# HV_PWR_STAGE.net
KiCad netlist of a schematic drawn in Altium Designer
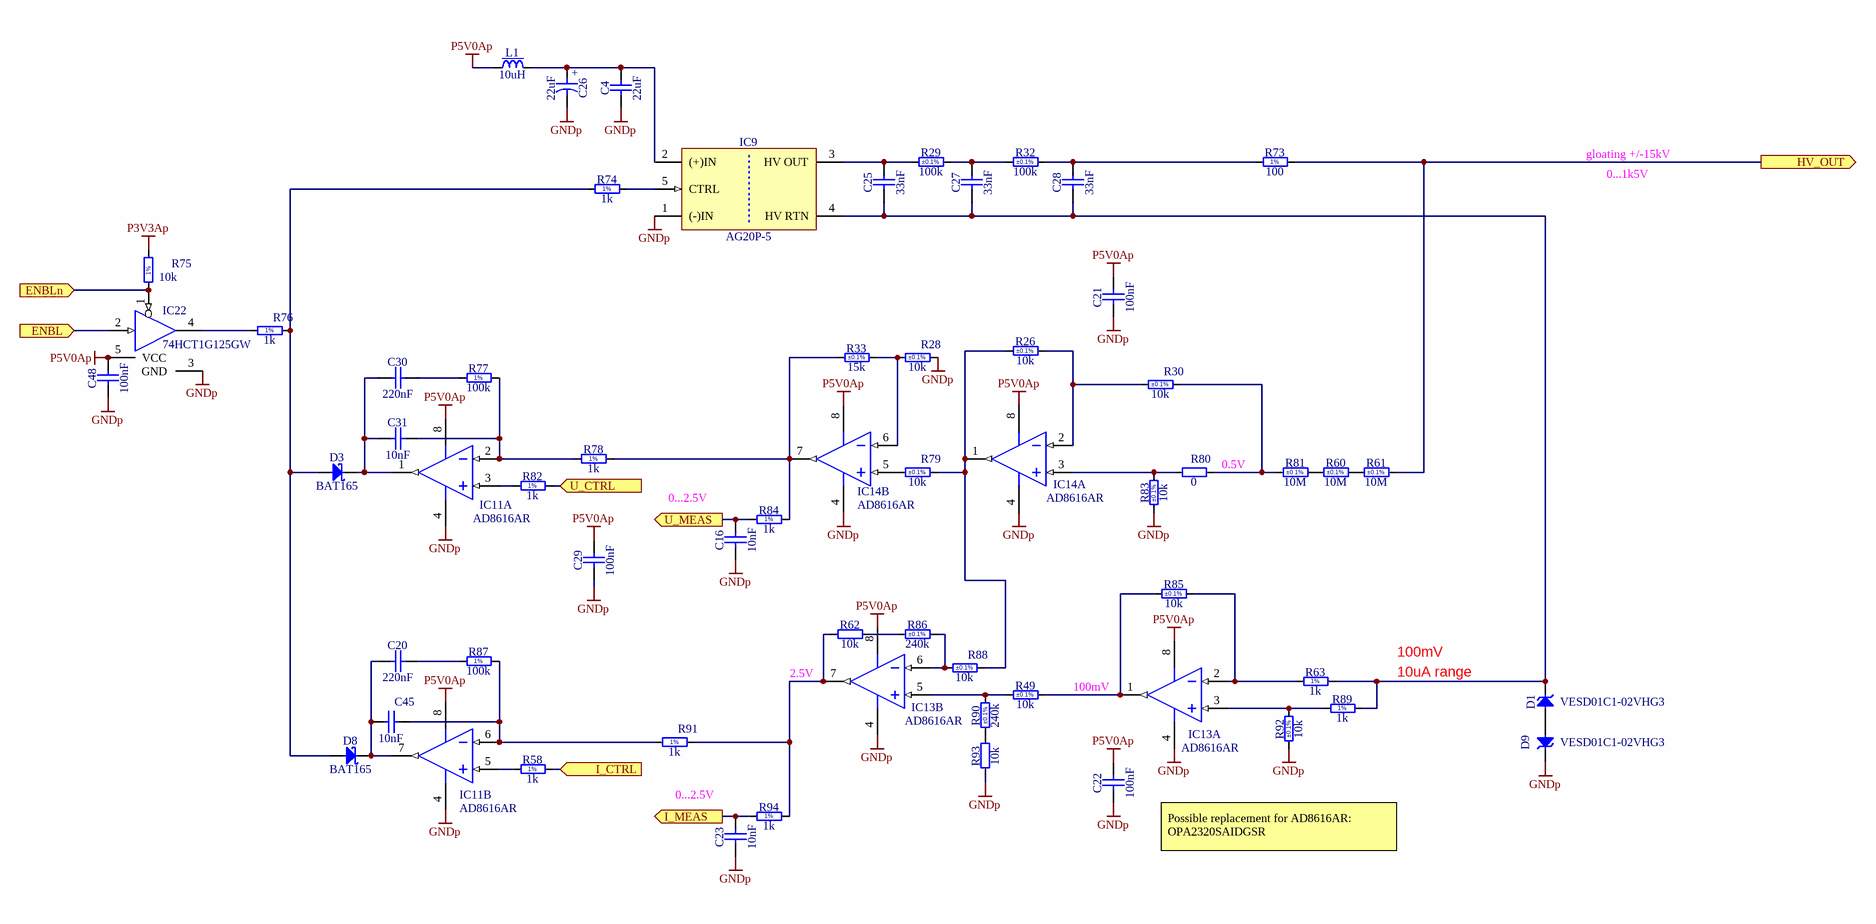
[diagram p0: HV_PWR_STAGE.SchDoc]

(export (version "E")
  (design (tool "Eeschema 10.0.6"))
  (components
    (comp (ref "C4")
      (value "22uF")
      (footprint "CAPC3216X180N")
      (description "Non-polarised capacitor")
      (fields
        (field (name "PART NUMBER") "CC1206_22UF_25V_20%_X5R")
        (field (name "VOLTAGE") "25V")
        (field (name "AUTHOR") "CERN DEM WB")
      )
      (libsource (lib "Capacitors") (part "Capacitor - non polarized"))
    )
    (comp (ref "C16")
      (value "10nF")
      (footprint "CAPC1005X55N")
      (description "Non-polarised capacitor")
      (fields
        (field (name "PART NUMBER") "CC0402_10NF_25V_10%_X7R")
        (field (name "VOLTAGE") "25V")
        (field (name "AUTHOR") "CERN DEM JLC")
      )
      (libsource (lib "Capacitors") (part "Capacitor - non polarized"))
    )
    (comp (ref "C20")
      (value "220nF")
      (footprint "CAPC1608X87N")
      (description "Non-polarised capacitor")
      (fields
        (field (name "PART NUMBER") "CC0603_220NF_10V_10%_X7R")
        (field (name "VOLTAGE") "10V")
        (field (name "AUTHOR") "CERN DEM JLC")
      )
      (libsource (lib "Capacitors") (part "Capacitor - non polarized"))
    )
    (comp (ref "C21")
      (value "100nF")
      (footprint "CAPC1005X55N")
      (description "Non-polarised capacitor")
      (fields
        (field (name "PART NUMBER") "CC0402_100NF_16V_10%_X7R")
        (field (name "VOLTAGE") "16V")
        (field (name "AUTHOR") "CERN DEM JLC")
      )
      (libsource (lib "Capacitors") (part "Capacitor - non polarized"))
    )
    (comp (ref "C22")
      (value "100nF")
      (footprint "CAPC1005X55N")
      (description "Non-polarised capacitor")
      (fields
        (field (name "PART NUMBER") "CC0402_100NF_16V_10%_X7R")
        (field (name "VOLTAGE") "16V")
        (field (name "AUTHOR") "CERN DEM JLC")
      )
      (libsource (lib "Capacitors") (part "Capacitor - non polarized"))
    )
    (comp (ref "C23")
      (value "10nF")
      (footprint "CAPC1005X55N")
      (description "Non-polarised capacitor")
      (fields
        (field (name "PART NUMBER") "CC0402_10NF_25V_10%_X7R")
        (field (name "VOLTAGE") "25V")
        (field (name "AUTHOR") "CERN DEM JLC")
      )
      (libsource (lib "Capacitors") (part "Capacitor - non polarized"))
    )
    (comp (ref "C25")
      (value "33nF")
      (footprint "CAPC5764X279N")
      (description "Non-polarised capacitor")
      (fields
        (field (name "PART NUMBER") "CC2225_33NF_2KV_10%_X7R")
        (field (name "VOLTAGE") "2KV")
        (field (name "AUTHOR") "CERN DEM JMW")
      )
      (libsource (lib "Capacitors") (part "Capacitor - non polarized"))
    )
    (comp (ref "C26")
      (value "22uF")
      (footprint "CAPMP3528X210N")
      (description "Polarised capacitor")
      (fields
        (field (name "PART NUMBER") "CTE3528-21_22UF_20V_10%")
        (field (name "VOLTAGE") "20V")
        (field (name "AUTHOR") "CERN DEM JLC")
      )
      (libsource (lib "Capacitors") (part "Capacitor - polarized"))
    )
    (comp (ref "C27")
      (value "33nF")
      (footprint "CAPC5764X279N")
      (description "Non-polarised capacitor")
      (fields
        (field (name "PART NUMBER") "CC2225_33NF_2KV_10%_X7R")
        (field (name "VOLTAGE") "2KV")
        (field (name "AUTHOR") "CERN DEM JMW")
      )
      (libsource (lib "Capacitors") (part "Capacitor - non polarized"))
    )
    (comp (ref "C28")
      (value "33nF")
      (footprint "CAPC5764X279N")
      (description "Non-polarised capacitor")
      (fields
        (field (name "PART NUMBER") "CC2225_33NF_2KV_10%_X7R")
        (field (name "VOLTAGE") "2KV")
        (field (name "AUTHOR") "CERN DEM JMW")
      )
      (libsource (lib "Capacitors") (part "Capacitor - non polarized"))
    )
    (comp (ref "C29")
      (value "100nF")
      (footprint "CAPC1005X55N")
      (description "Non-polarised capacitor")
      (fields
        (field (name "PART NUMBER") "CC0402_100NF_16V_10%_X7R")
        (field (name "VOLTAGE") "16V")
        (field (name "AUTHOR") "CERN DEM JLC")
      )
      (libsource (lib "Capacitors") (part "Capacitor - non polarized"))
    )
    (comp (ref "C30")
      (value "220nF")
      (footprint "CAPC1608X87N")
      (description "Non-polarised capacitor")
      (fields
        (field (name "PART NUMBER") "CC0603_220NF_10V_10%_X7R")
        (field (name "VOLTAGE") "10V")
        (field (name "AUTHOR") "CERN DEM JLC")
      )
      (libsource (lib "Capacitors") (part "Capacitor - non polarized"))
    )
    (comp (ref "C31")
      (value "10nF")
      (footprint "CAPC1608X87N")
      (description "Non-polarised capacitor")
      (fields
        (field (name "PART NUMBER") "CC0603_10NF_50V_5%_C0G")
        (field (name "VOLTAGE") "50V")
        (field (name "AUTHOR") "CERN DEM JLC")
      )
      (libsource (lib "Capacitors") (part "Capacitor - non polarized"))
    )
    (comp (ref "C45")
      (value "10nF")
      (footprint "CAPC1608X87N")
      (description "Non-polarised capacitor")
      (fields
        (field (name "PART NUMBER") "CC0603_10NF_50V_5%_C0G")
        (field (name "VOLTAGE") "50V")
        (field (name "AUTHOR") "CERN DEM JLC")
      )
      (libsource (lib "Capacitors") (part "Capacitor - non polarized"))
    )
    (comp (ref "C48")
      (value "100nF")
      (footprint "CAPC1005X55N")
      (description "Non-polarised capacitor")
      (fields
        (field (name "PART NUMBER") "CC0402_100NF_16V_10%_X7R")
        (field (name "VOLTAGE") "16V")
        (field (name "AUTHOR") "CERN DEM JLC")
      )
      (libsource (lib "Capacitors") (part "Capacitor - non polarized"))
    )
    (comp (ref "D1")
      (value "VESD01C1-02VHG3")
      (footprint "SODFL1608X70N")
      (description "Transient Voltage Suppressor Diode (Uni-Directional)")
      (fields
        (field (name "VOLTAGE") "1V")
        (field (name "POWER") "100W")
        (field (name "AUTHOR") "CERN DEM BC")
      )
      (libsource (lib "ICs And Semiconductors") (part "Diode TVS Uni-Directional"))
    )
    (comp (ref "D3")
      (value "BAT165")
      (footprint "SOD2512X110N")
      (description "Schottky Diode")
      (fields
        (field (name "VOLTAGE") "40V")
        (field (name "POWER") "750mA")
        (field (name "AUTHOR") "CERN DEM JLC")
      )
      (libsource (lib "ICs And Semiconductors") (part "Diode Schottky"))
    )
    (comp (ref "D8")
      (value "BAT165")
      (footprint "SOD2512X110N")
      (description "Schottky Diode")
      (fields
        (field (name "VOLTAGE") "40V")
        (field (name "POWER") "750mA")
        (field (name "AUTHOR") "CERN DEM JLC")
      )
      (libsource (lib "ICs And Semiconductors") (part "Diode Schottky"))
    )
    (comp (ref "D9")
      (value "VESD01C1-02VHG3")
      (footprint "SODFL1608X70N")
      (description "Transient Voltage Suppressor Diode (Uni-Directional)")
      (fields
        (field (name "VOLTAGE") "1V")
        (field (name "POWER") "100W")
        (field (name "AUTHOR") "CERN DEM BC")
      )
      (libsource (lib "ICs And Semiconductors") (part "Diode TVS Uni-Directional"))
    )
    (comp (ref "IC9")
      (value "AG20P-5")
      (footprint "DCDC_XPPOWER_AG0-2KV")
      (description "XP POWER, AG Series, DC/HVDC Converter")
      (fields (field (name "MANUFACTURER") "XP POWER") (field (name "AUTHOR") "CERN DEM BC"))
      (libsource (lib "ICs And Semiconductors") (part "DCDC_XPPOWER_AG"))
    )
    (comp (ref "IC11")
      (value "AD8616AR")
      (footprint "ADI-R-8_N")
      (fields
        (field (name "MANUFACTURER") "Analog Devices")
        (field (name "GENERIC PART NUMBER") "AD8616")
        (field (name "MANUFACTURER1 PART NUMBER") "OPA2320SAIDGSR")
      )
      (libsource (lib "Altium Content Vault") (part "ADI-OP29X-R-8"))
    )
    (comp (ref "IC13")
      (value "AD8616AR")
      (footprint "ADI-R-8_N")
      (fields
        (field (name "MANUFACTURER") "Analog Devices")
        (field (name "GENERIC PART NUMBER") "AD8616")
        (field (name "MANUFACTURER1 PART NUMBER") "OPA2320SAIDGSR")
      )
      (libsource (lib "Altium Content Vault") (part "ADI-OP29X-R-8"))
    )
    (comp (ref "IC14")
      (value "AD8616AR")
      (footprint "ADI-R-8_N")
      (fields
        (field (name "MANUFACTURER") "Analog Devices")
        (field (name "GENERIC PART NUMBER") "AD8616")
        (field (name "MANUFACTURER1 PART NUMBER") "OPA2320SAIDGSR")
      )
      (libsource (lib "Altium Content Vault") (part "ADI-OP29X-R-8"))
    )
    (comp (ref "IC22")
      (value "74HCT1G125GW")
      (footprint "SOT65P210X110-5N")
      (description "Single Bus Buffer Gate With 3-State Output")
      (fields (field (name "MANUFACTURER") "NEXPERIA") (field (name "AUTHOR") "CERN DEM JMW"))
      (libsource (lib "ICs And Semiconductors") (part "741G125"))
    )
    (comp (ref "L1")
      (value "10uH")
      (footprint "IND_BOURNS_PM43")
      (description "Inductor With Core")
      (fields
        (field (name "PART NUMBER") "IND_10UH_20%_BOURNS_PM43")
        (field (name "POWER") "1.15A")
        (field (name "AUTHOR") "CERN DEM JLC")
      )
      (libsource (lib "Inductors & Transformers") (part "Inductor With Magnetic core"))
    )
    (comp (ref "R26")
      (value "10k")
      (footprint "RESC1608X55N")
      (description "Resistor - 0.1%")
      (fields
        (field (name "TOLERANCE") "±0.1%")
        (field (name "PART NUMBER") "R0603_10K_0.1%_0.063W_10PPM")
        (field (name "POWER") "0.063W")
        (field (name "AUTHOR") "CERN DEM JLC")
      )
      (libsource (lib "Resistors") (part "Resistor - 0.1%"))
    )
    (comp (ref "R28")
      (value "10k")
      (footprint "RESC1608X55N")
      (description "Resistor - 0.1%")
      (fields
        (field (name "TOLERANCE") "±0.1%")
        (field (name "PART NUMBER") "R0603_10K_0.1%_0.063W_10PPM")
        (field (name "POWER") "0.063W")
        (field (name "AUTHOR") "CERN DEM JLC")
      )
      (libsource (lib "Resistors") (part "Resistor - 0.1%"))
    )
    (comp (ref "R29")
      (value "100k")
      (footprint "RESC3216X50N")
      (description "Resistor - 0.1%")
      (fields
        (field (name "TOLERANCE") "±0.1%")
        (field (name "PART NUMBER") "R1206_100K_0.1%_0.4W_25PPM_VISHAY_PAT")
        (field (name "POWER") "0.4W")
        (field (name "AUTHOR") "CERN DEM MR")
      )
      (libsource (lib "Resistors") (part "Resistor - 0.1%"))
    )
    (comp (ref "R30")
      (value "10k")
      (footprint "RESC1608X55N")
      (description "Resistor - 0.1%")
      (fields
        (field (name "TOLERANCE") "±0.1%")
        (field (name "PART NUMBER") "R0603_10K_0.1%_0.063W_10PPM")
        (field (name "POWER") "0.063W")
        (field (name "AUTHOR") "CERN DEM JLC")
      )
      (libsource (lib "Resistors") (part "Resistor - 0.1%"))
    )
    (comp (ref "R32")
      (value "100k")
      (footprint "RESC3216X50N")
      (description "Resistor - 0.1%")
      (fields
        (field (name "TOLERANCE") "±0.1%")
        (field (name "PART NUMBER") "R1206_100K_0.1%_0.4W_25PPM_VISHAY_PAT")
        (field (name "POWER") "0.4W")
        (field (name "AUTHOR") "CERN DEM MR")
      )
      (libsource (lib "Resistors") (part "Resistor - 0.1%"))
    )
    (comp (ref "R33")
      (value "15k")
      (footprint "RESC1608X55N")
      (description "Resistor - 0.1%")
      (fields
        (field (name "TOLERANCE") "±0.1%")
        (field (name "PART NUMBER") "R0603_15K_0.1%_0.063W_10PPM")
        (field (name "POWER") "0.063W")
        (field (name "AUTHOR") "CERN DEM JLC")
      )
      (libsource (lib "Resistors") (part "Resistor - 0.1%"))
    )
    (comp (ref "R49")
      (value "10k")
      (footprint "RESC1608X55N")
      (description "Resistor - 0.1%")
      (fields
        (field (name "TOLERANCE") "±0.1%")
        (field (name "PART NUMBER") "R0603_10K_0.1%_0.063W_10PPM")
        (field (name "POWER") "0.063W")
        (field (name "AUTHOR") "CERN DEM JLC")
      )
      (libsource (lib "Resistors") (part "Resistor - 0.1%"))
    )
    (comp (ref "R58")
      (value "1k")
      (footprint "RESC1005X40N")
      (description "Resistor - 1%")
      (fields
        (field (name "PART NUMBER") "R0402_1K_1%_0.0625W_100PPM")
        (field (name "POWER") "0.0625W")
        (field (name "AUTHOR") "CERN DEM JLC")
      )
      (libsource (lib "Resistors") (part "Resistor - 1%"))
    )
    (comp (ref "R60")
      (value "10M")
      (footprint "RESC5025X65N")
      (description "RES, HV, 2010, 10 Mohm, 0.1%, 25 ppm, 1W")
      (fields
        (field (name "PART NUMBER") "R1210_1M0_0.1%_1W_25ppm_HVCB2010BDE10M0")
        (field (name "POWER") "1W")
        (field (name "TOLERANCE") "±0.1%")
        (field (name "AUTHOR") "GK")
      )
      (libsource (lib "Passives_RC") (part "R1210_1M0_0.1%_1W_25ppm_HVCB2010BDE10M0"))
    )
    (comp (ref "R61")
      (value "10M")
      (footprint "RESC5025X65N")
      (description "RES, HV, 2010, 10 Mohm, 0.1%, 25 ppm, 1W")
      (fields
        (field (name "PART NUMBER") "R1210_1M0_0.1%_1W_25ppm_HVCB2010BDE10M0")
        (field (name "POWER") "1W")
        (field (name "TOLERANCE") "±0.1%")
        (field (name "AUTHOR") "GK")
      )
      (libsource (lib "Passives_RC") (part "R1210_1M0_0.1%_1W_25ppm_HVCB2010BDE10M0"))
    )
    (comp (ref "R62")
      (value "10k")
      (footprint "RESC1005X40N")
      (description "Resistor - 1%")
      (fields
        (field (name "PART NUMBER") "R0402_10K_1%_0.0625W_100PPM")
        (field (name "POWER") "0.0625W")
        (field (name "AUTHOR") "CERN DEM JLC")
      )
      (libsource (lib "") (part "Resistor - 1%_1"))
    )
    (comp (ref "R63")
      (value "1k")
      (footprint "RESC1005X40N")
      (description "Resistor - 1%")
      (fields
        (field (name "PART NUMBER") "R0402_1K_1%_0.0625W_100PPM")
        (field (name "POWER") "0.0625W")
        (field (name "AUTHOR") "CERN DEM JLC")
      )
      (libsource (lib "Resistors") (part "Resistor - 1%"))
    )
    (comp (ref "R73")
      (value "100")
      (footprint "RESC6331X70N")
      (description "Resistor - 1%")
      (fields
        (field (name "PART NUMBER") "R2512_100R_1%_1.5W_100PPM_VISHAY_CRCW-HP e3")
        (field (name "POWER") "1.5W")
        (field (name "AUTHOR") "CERN DEM JLC")
      )
      (libsource (lib "Resistors") (part "Resistor - 1%"))
    )
    (comp (ref "R74")
      (value "1k")
      (footprint "RESC1608X55N")
      (description "Resistor - 1%")
      (fields
        (field (name "PART NUMBER") "R0603_1K_1%_0.1W_100PPM")
        (field (name "POWER") "0.1W")
        (field (name "AUTHOR") "CERN DEM JLC")
      )
      (libsource (lib "Resistors") (part "Resistor - 1%"))
    )
    (comp (ref "R75")
      (value "10k")
      (footprint "RESC1005X40N")
      (description "Resistor - 1%")
      (fields
        (field (name "PART NUMBER") "R0402_10K_1%_0.0625W_100PPM")
        (field (name "POWER") "0.0625W")
        (field (name "AUTHOR") "CERN DEM JLC")
      )
      (libsource (lib "Resistors") (part "Resistor - 1%"))
    )
    (comp (ref "R76")
      (value "1k")
      (footprint "RESC1005X40N")
      (description "Resistor - 1%")
      (fields
        (field (name "PART NUMBER") "R0402_1K_1%_0.0625W_100PPM")
        (field (name "POWER") "0.0625W")
        (field (name "AUTHOR") "CERN DEM JLC")
      )
      (libsource (lib "Resistors") (part "Resistor - 1%"))
    )
    (comp (ref "R77")
      (value "100k")
      (footprint "RESC1608X55N")
      (description "Resistor - 1%")
      (fields
        (field (name "PART NUMBER") "R0603_100K_1%_0.1W_100PPM")
        (field (name "POWER") "0.1W")
        (field (name "AUTHOR") "CERN DEM JLC")
      )
      (libsource (lib "Resistors") (part "Resistor - 1%"))
    )
    (comp (ref "R78")
      (value "1k")
      (footprint "RESC1005X40N")
      (description "Resistor - 1%")
      (fields
        (field (name "PART NUMBER") "R0402_1K_1%_0.0625W_100PPM")
        (field (name "POWER") "0.0625W")
        (field (name "AUTHOR") "CERN DEM JLC")
      )
      (libsource (lib "Resistors") (part "Resistor - 1%"))
    )
    (comp (ref "R79")
      (value "10k")
      (footprint "RESC1608X55N")
      (description "Resistor - 0.1%")
      (fields
        (field (name "TOLERANCE") "±0.1%")
        (field (name "PART NUMBER") "R0603_10K_0.1%_0.063W_10PPM")
        (field (name "POWER") "0.063W")
        (field (name "AUTHOR") "CERN DEM JLC")
      )
      (libsource (lib "Resistors") (part "Resistor - 0.1%"))
    )
    (comp (ref "R80")
      (value "0")
      (footprint "RESC1005X40N")
      (description "Resistor")
      (fields
        (field (name "PART NUMBER") "R0402_0R_JUMPER")
        (field (name "MANUFACTURER") "GENERIC")
        (field (name "AUTHOR") "CERN DEM JLC")
      )
      (libsource (lib "Resistors") (part "Resistor"))
    )
    (comp (ref "R81")
      (value "10M")
      (footprint "RESC5025X65N")
      (description "RES, HV, 2010, 10 Mohm, 0.1%, 25 ppm, 1W")
      (fields
        (field (name "PART NUMBER") "R1210_1M0_0.1%_1W_25ppm_HVCB2010BDE10M0")
        (field (name "POWER") "1W")
        (field (name "TOLERANCE") "±0.1%")
        (field (name "AUTHOR") "GK")
      )
      (libsource (lib "Passives_RC") (part "R1210_1M0_0.1%_1W_25ppm_HVCB2010BDE10M0"))
    )
    (comp (ref "R82")
      (value "1k")
      (footprint "RESC1005X40N")
      (description "Resistor - 1%")
      (fields
        (field (name "PART NUMBER") "R0402_1K_1%_0.0625W_100PPM")
        (field (name "POWER") "0.0625W")
        (field (name "AUTHOR") "CERN DEM JLC")
      )
      (libsource (lib "Resistors") (part "Resistor - 1%"))
    )
    (comp (ref "R83")
      (value "10k")
      (footprint "RESC1608X55N")
      (description "Resistor - 0.1%")
      (fields
        (field (name "TOLERANCE") "±0.1%")
        (field (name "PART NUMBER") "R0603_10K_0.1%_0.063W_10PPM")
        (field (name "POWER") "0.063W")
        (field (name "AUTHOR") "CERN DEM JLC")
      )
      (libsource (lib "Resistors") (part "Resistor - 0.1%"))
    )
    (comp (ref "R84")
      (value "1k")
      (footprint "RESC1005X40N")
      (description "Resistor - 1%")
      (fields
        (field (name "PART NUMBER") "R0402_1K_1%_0.0625W_100PPM")
        (field (name "POWER") "0.0625W")
        (field (name "AUTHOR") "CERN DEM JLC")
      )
      (libsource (lib "Resistors") (part "Resistor - 1%"))
    )
    (comp (ref "R85")
      (value "10k")
      (footprint "RESC1608X55N")
      (description "Resistor - 0.1%")
      (fields
        (field (name "TOLERANCE") "±0.1%")
        (field (name "PART NUMBER") "R0603_10K_0.1%_0.063W_10PPM")
        (field (name "POWER") "0.063W")
        (field (name "AUTHOR") "CERN DEM JLC")
      )
      (libsource (lib "Resistors") (part "Resistor - 0.1%"))
    )
    (comp (ref "R86")
      (value "240k")
      (footprint "RESC1608X55N")
      (description "Resistor - 0.1%")
      (fields
        (field (name "TOLERANCE") "±0.1%")
        (field (name "PART NUMBER") "R0603_240K_0.1%_0.063W_10PPM")
        (field (name "POWER") "0.063W")
        (field (name "AUTHOR") "CERN DEM BC")
      )
      (libsource (lib "Resistors") (part "Resistor - 0.1%"))
    )
    (comp (ref "R87")
      (value "100k")
      (footprint "RESC1608X55N")
      (description "Resistor - 1%")
      (fields
        (field (name "PART NUMBER") "R0603_100K_1%_0.1W_100PPM")
        (field (name "POWER") "0.1W")
        (field (name "AUTHOR") "CERN DEM JLC")
      )
      (libsource (lib "Resistors") (part "Resistor - 1%"))
    )
    (comp (ref "R88")
      (value "10k")
      (footprint "RESC1608X55N")
      (description "Resistor - 0.1%")
      (fields
        (field (name "TOLERANCE") "±0.1%")
        (field (name "PART NUMBER") "R0603_10K_0.1%_0.063W_10PPM")
        (field (name "POWER") "0.063W")
        (field (name "AUTHOR") "CERN DEM JLC")
      )
      (libsource (lib "Resistors") (part "Resistor - 0.1%"))
    )
    (comp (ref "R89")
      (value "1k")
      (footprint "RESC1005X40N")
      (description "Resistor - 1%")
      (fields
        (field (name "PART NUMBER") "R0402_1K_1%_0.0625W_100PPM")
        (field (name "POWER") "0.0625W")
        (field (name "AUTHOR") "CERN DEM JLC")
      )
      (libsource (lib "Resistors") (part "Resistor - 1%"))
    )
    (comp (ref "R90")
      (value "240k")
      (footprint "RESC1608X55N")
      (description "Resistor - 0.1%")
      (fields
        (field (name "TOLERANCE") "±0.1%")
        (field (name "PART NUMBER") "R0603_240K_0.1%_0.063W_10PPM")
        (field (name "POWER") "0.063W")
        (field (name "AUTHOR") "CERN DEM BC")
      )
      (libsource (lib "Resistors") (part "Resistor - 0.1%"))
    )
    (comp (ref "R91")
      (value "1k")
      (footprint "RESC1005X40N")
      (description "Resistor - 1%")
      (fields
        (field (name "PART NUMBER") "R0402_1K_1%_0.0625W_100PPM")
        (field (name "POWER") "0.0625W")
        (field (name "AUTHOR") "CERN DEM JLC")
      )
      (libsource (lib "Resistors") (part "Resistor - 1%"))
    )
    (comp (ref "R92")
      (value "10k")
      (footprint "RESC1608X55N")
      (description "Resistor - 0.1%")
      (fields
        (field (name "TOLERANCE") "±0.1%")
        (field (name "PART NUMBER") "R0603_10K_0.1%_0.063W_10PPM")
        (field (name "POWER") "0.063W")
        (field (name "AUTHOR") "CERN DEM JLC")
      )
      (libsource (lib "Resistors") (part "Resistor - 0.1%"))
    )
    (comp (ref "R93")
      (value "10k")
      (footprint "RESC1005X40N")
      (description "Resistor - 1%")
      (fields
        (field (name "PART NUMBER") "R0402_10K_1%_0.0625W_100PPM")
        (field (name "POWER") "0.0625W")
        (field (name "AUTHOR") "CERN DEM JLC")
      )
      (libsource (lib "") (part "Resistor - 1%_1"))
    )
    (comp (ref "R94")
      (value "1k")
      (footprint "RESC1005X40N")
      (description "Resistor - 1%")
      (fields
        (field (name "PART NUMBER") "R0402_1K_1%_0.0625W_100PPM")
        (field (name "POWER") "0.0625W")
        (field (name "AUTHOR") "CERN DEM JLC")
      )
      (libsource (lib "Resistors") (part "Resistor - 1%"))
    )
  )
  (nets
    (net (code "1") (name "/ENBL") (class "Default")
      (node (ref "IC22") (pin "2") (pinfunction "IN_2") (pintype "input"))
    )
    (net (code "2") (name "/ENBLn") (class "Default")
      (node (ref "IC22") (pin "1") (pinfunction "~{G}_1") (pintype "input"))
      (node (ref "R75") (pin "1") (pinfunction "1_1") (pintype "passive"))
    )
    (net (code "3") (name "/HV_OUT") (class "Default")
      (node (ref "R61") (pin "2") (pinfunction "2_2") (pintype "passive"))
      (node (ref "R73") (pin "2") (pinfunction "2_2") (pintype "passive"))
    )
    (net (code "4") (name "/I_CTRL") (class "Default")
      (node (ref "R58") (pin "2") (pinfunction "2_2") (pintype "passive"))
    )
    (net (code "5") (name "/I_MEAS") (class "Default")
      (node (ref "C23") (pin "2") (pinfunction "2_2") (pintype "passive"))
      (node (ref "R94") (pin "1") (pinfunction "1_1") (pintype "passive"))
    )
    (net (code "6") (name "/U_CTRL") (class "Default")
      (node (ref "R82") (pin "2") (pinfunction "2_2") (pintype "passive"))
    )
    (net (code "7") (name "/U_MEAS") (class "Default")
      (node (ref "C16") (pin "2") (pinfunction "2_2") (pintype "passive"))
      (node (ref "R84") (pin "1") (pinfunction "1_1") (pintype "passive"))
    )
    (net (code "8") (name "GNDp") (class "Default")
      (node (ref "C16") (pin "1") (pinfunction "1_1") (pintype "passive"))
      (node (ref "C21") (pin "1") (pinfunction "1_1") (pintype "passive"))
      (node (ref "C22") (pin "1") (pinfunction "1_1") (pintype "passive"))
      (node (ref "C23") (pin "1") (pinfunction "1_1") (pintype "passive"))
      (node (ref "C26") (pin "2") (pinfunction "2_2") (pintype "passive"))
      (node (ref "C29") (pin "1") (pinfunction "1_1") (pintype "passive"))
      (node (ref "C4") (pin "1") (pinfunction "1_1") (pintype "passive"))
      (node (ref "C48") (pin "1") (pinfunction "1_1") (pintype "passive"))
      (node (ref "D9") (pin "1") (pinfunction "C_1") (pintype "passive"))
      (node (ref "IC11") (pin "4") (pinfunction "-V_4") (pintype "power_in"))
      (node (ref "IC13") (pin "4") (pinfunction "-V_4") (pintype "power_in"))
      (node (ref "IC14") (pin "4") (pinfunction "-V_4") (pintype "power_in"))
      (node (ref "IC22") (pin "3") (pinfunction "GND_3") (pintype "power_in"))
      (node (ref "IC9") (pin "1") (pinfunction "(-)IN_1") (pintype "power_in"))
      (node (ref "R28") (pin "2") (pinfunction "2_2") (pintype "passive"))
      (node (ref "R83") (pin "1") (pinfunction "1_1") (pintype "passive"))
      (node (ref "R92") (pin "1") (pinfunction "1_1") (pintype "passive"))
      (node (ref "R93") (pin "1") (pinfunction "1_1") (pintype "passive"))
    )
    (net (code "9") (name "Net-(C20-Pad2)") (class "Default")
      (node (ref "C20") (pin "2") (pinfunction "2_2") (pintype "passive"))
      (node (ref "R87") (pin "1") (pinfunction "1_1") (pintype "passive"))
    )
    (net (code "10") (name "Net-(C27-Pad2)") (class "Default")
      (node (ref "C27") (pin "2") (pinfunction "2_2") (pintype "passive"))
      (node (ref "R29") (pin "2") (pinfunction "2_2") (pintype "passive"))
      (node (ref "R32") (pin "1") (pinfunction "1_1") (pintype "passive"))
    )
    (net (code "11") (name "Net-(C28-Pad2)") (class "Default")
      (node (ref "C28") (pin "2") (pinfunction "2_2") (pintype "passive"))
      (node (ref "R32") (pin "2") (pinfunction "2_2") (pintype "passive"))
      (node (ref "R73") (pin "1") (pinfunction "1_1") (pintype "passive"))
    )
    (net (code "12") (name "Net-(C30-Pad2)") (class "Default")
      (node (ref "C30") (pin "2") (pinfunction "2_2") (pintype "passive"))
      (node (ref "R77") (pin "1") (pinfunction "1_1") (pintype "passive"))
    )
    (net (code "13") (name "Net-(D1-A)") (class "Default")
      (node (ref "D1") (pin "2") (pinfunction "A_2") (pintype "passive"))
      (node (ref "D9") (pin "2") (pinfunction "A_2") (pintype "passive"))
    )
    (net (code "14") (name "Net-(D1-C)") (class "Default")
      (node (ref "C25") (pin "1") (pinfunction "1_1") (pintype "passive"))
      (node (ref "C27") (pin "1") (pinfunction "1_1") (pintype "passive"))
      (node (ref "C28") (pin "1") (pinfunction "1_1") (pintype "passive"))
      (node (ref "D1") (pin "1") (pinfunction "C_1") (pintype "passive"))
      (node (ref "IC9") (pin "4") (pinfunction "HV_RTN_4") (pintype "power_in"))
      (node (ref "R63") (pin "2") (pinfunction "2_2") (pintype "passive"))
      (node (ref "R89") (pin "2") (pinfunction "2_2") (pintype "passive"))
    )
    (net (code "15") (name "Net-(D3-A)") (class "Default")
      (node (ref "D3") (pin "2") (pinfunction "A_2") (pintype "passive"))
      (node (ref "D8") (pin "2") (pinfunction "A_2") (pintype "passive"))
      (node (ref "R74") (pin "1") (pinfunction "1_1") (pintype "passive"))
      (node (ref "R76") (pin "2") (pinfunction "2_2") (pintype "passive"))
    )
    (net (code "16") (name "Net-(D3-C)") (class "Default")
      (node (ref "C30") (pin "1") (pinfunction "1_1") (pintype "passive"))
      (node (ref "C31") (pin "1") (pinfunction "1_1") (pintype "passive"))
      (node (ref "D3") (pin "1") (pinfunction "C_1") (pintype "passive"))
      (node (ref "IC11") (pin "1") (pinfunction "OUT_A_1") (pintype "output"))
    )
    (net (code "17") (name "Net-(D8-C)") (class "Default")
      (node (ref "C20") (pin "1") (pinfunction "1_1") (pintype "passive"))
      (node (ref "C45") (pin "1") (pinfunction "1_1") (pintype "passive"))
      (node (ref "D8") (pin "1") (pinfunction "C_1") (pintype "passive"))
      (node (ref "IC11") (pin "7") (pinfunction "OUT_B_7") (pintype "output"))
    )
    (net (code "18") (name "Net-(IC9-(+)IN)") (class "Default")
      (node (ref "C26") (pin "1") (pinfunction "1_1") (pintype "passive"))
      (node (ref "C4") (pin "2") (pinfunction "2_2") (pintype "passive"))
      (node (ref "IC9") (pin "2") (pinfunction "(+)IN_2") (pintype "power_in"))
      (node (ref "L1") (pin "2") (pinfunction "2_2") (pintype "passive"))
    )
    (net (code "19") (name "Net-(IC9-CTRL)") (class "Default")
      (node (ref "IC9") (pin "5") (pinfunction "CTRL_5") (pintype "input"))
      (node (ref "R74") (pin "2") (pinfunction "2_2") (pintype "passive"))
    )
    (net (code "20") (name "Net-(IC9-HV_OUT)") (class "Default")
      (node (ref "C25") (pin "2") (pinfunction "2_2") (pintype "passive"))
      (node (ref "IC9") (pin "3") (pinfunction "HV_OUT_3") (pintype "power_in"))
      (node (ref "R29") (pin "1") (pinfunction "1_1") (pintype "passive"))
    )
    (net (code "21") (name "Net-(IC11A-+IN_A)") (class "Default")
      (node (ref "IC11") (pin "3") (pinfunction "+IN_A_3") (pintype "input"))
      (node (ref "R82") (pin "1") (pinfunction "1_1") (pintype "passive"))
    )
    (net (code "22") (name "Net-(IC11A--IN_A)") (class "Default")
      (node (ref "C31") (pin "2") (pinfunction "2_2") (pintype "passive"))
      (node (ref "IC11") (pin "2") (pinfunction "-IN_A_2") (pintype "input"))
      (node (ref "R77") (pin "2") (pinfunction "2_2") (pintype "passive"))
      (node (ref "R78") (pin "1") (pinfunction "1_1") (pintype "passive"))
    )
    (net (code "23") (name "Net-(IC11B-+IN_B)") (class "Default")
      (node (ref "IC11") (pin "5") (pinfunction "+IN_B_5") (pintype "input"))
      (node (ref "R58") (pin "1") (pinfunction "1_1") (pintype "passive"))
    )
    (net (code "24") (name "Net-(IC11B--IN_B)") (class "Default")
      (node (ref "C45") (pin "2") (pinfunction "2_2") (pintype "passive"))
      (node (ref "IC11") (pin "6") (pinfunction "-IN_B_6") (pintype "input"))
      (node (ref "R87") (pin "2") (pinfunction "2_2") (pintype "passive"))
      (node (ref "R91") (pin "1") (pinfunction "1_1") (pintype "passive"))
    )
    (net (code "25") (name "Net-(IC13A-+IN_A)") (class "Default")
      (node (ref "IC13") (pin "3") (pinfunction "+IN_A_3") (pintype "input"))
      (node (ref "R89") (pin "1") (pinfunction "1_1") (pintype "passive"))
      (node (ref "R92") (pin "2") (pinfunction "2_2") (pintype "passive"))
    )
    (net (code "26") (name "Net-(IC13A--IN_A)") (class "Default")
      (node (ref "IC13") (pin "2") (pinfunction "-IN_A_2") (pintype "input"))
      (node (ref "R63") (pin "1") (pinfunction "1_1") (pintype "passive"))
      (node (ref "R85") (pin "2") (pinfunction "2_2") (pintype "passive"))
    )
    (net (code "27") (name "Net-(IC13A-OUT_A)") (class "Default")
      (node (ref "IC13") (pin "1") (pinfunction "OUT_A_1") (pintype "output"))
      (node (ref "R49") (pin "2") (pinfunction "2_2") (pintype "passive"))
      (node (ref "R85") (pin "1") (pinfunction "1_1") (pintype "passive"))
    )
    (net (code "28") (name "Net-(IC13B-+IN_B)") (class "Default")
      (node (ref "IC13") (pin "5") (pinfunction "+IN_B_5") (pintype "input"))
      (node (ref "R49") (pin "1") (pinfunction "1_1") (pintype "passive"))
      (node (ref "R90") (pin "2") (pinfunction "2_2") (pintype "passive"))
    )
    (net (code "29") (name "Net-(IC13B--IN_B)") (class "Default")
      (node (ref "IC13") (pin "6") (pinfunction "-IN_B_6") (pintype "input"))
      (node (ref "R86") (pin "2") (pinfunction "2_2") (pintype "passive"))
      (node (ref "R88") (pin "1") (pinfunction "1_1") (pintype "passive"))
    )
    (net (code "30") (name "Net-(IC13B-OUT_B)") (class "Default")
      (node (ref "IC13") (pin "7") (pinfunction "OUT_B_7") (pintype "output"))
      (node (ref "R62") (pin "1") (pinfunction "1_1") (pintype "passive"))
      (node (ref "R91") (pin "2") (pinfunction "2_2") (pintype "passive"))
      (node (ref "R94") (pin "2") (pinfunction "2_2") (pintype "passive"))
    )
    (net (code "31") (name "Net-(IC14A-+IN_A)") (class "Default")
      (node (ref "IC14") (pin "3") (pinfunction "+IN_A_3") (pintype "input"))
      (node (ref "R80") (pin "1") (pinfunction "1_1") (pintype "passive"))
      (node (ref "R83") (pin "2") (pinfunction "2_2") (pintype "passive"))
    )
    (net (code "32") (name "Net-(IC14A--IN_A)") (class "Default")
      (node (ref "IC14") (pin "2") (pinfunction "-IN_A_2") (pintype "input"))
      (node (ref "R26") (pin "2") (pinfunction "2_2") (pintype "passive"))
      (node (ref "R30") (pin "1") (pinfunction "1_1") (pintype "passive"))
    )
    (net (code "33") (name "Net-(IC14A-OUT_A)") (class "Default")
      (node (ref "IC14") (pin "1") (pinfunction "OUT_A_1") (pintype "output"))
      (node (ref "R26") (pin "1") (pinfunction "1_1") (pintype "passive"))
      (node (ref "R79") (pin "2") (pinfunction "2_2") (pintype "passive"))
      (node (ref "R88") (pin "2") (pinfunction "2_2") (pintype "passive"))
    )
    (net (code "34") (name "Net-(IC14B-+IN_B)") (class "Default")
      (node (ref "IC14") (pin "5") (pinfunction "+IN_B_5") (pintype "input"))
      (node (ref "R79") (pin "1") (pinfunction "1_1") (pintype "passive"))
    )
    (net (code "35") (name "Net-(IC14B--IN_B)") (class "Default")
      (node (ref "IC14") (pin "6") (pinfunction "-IN_B_6") (pintype "input"))
      (node (ref "R28") (pin "1") (pinfunction "1_1") (pintype "passive"))
      (node (ref "R33") (pin "2") (pinfunction "2_2") (pintype "passive"))
    )
    (net (code "36") (name "Net-(IC14B-OUT_B)") (class "Default")
      (node (ref "IC14") (pin "7") (pinfunction "OUT_B_7") (pintype "output"))
      (node (ref "R33") (pin "1") (pinfunction "1_1") (pintype "passive"))
      (node (ref "R78") (pin "2") (pinfunction "2_2") (pintype "passive"))
      (node (ref "R84") (pin "2") (pinfunction "2_2") (pintype "passive"))
    )
    (net (code "37") (name "Net-(IC22-OUT)") (class "Default")
      (node (ref "IC22") (pin "4") (pinfunction "OUT_4") (pintype "tri_state"))
      (node (ref "R76") (pin "1") (pinfunction "1_1") (pintype "passive"))
    )
    (net (code "38") (name "Net-(R30-Pad2)") (class "Default")
      (node (ref "R30") (pin "2") (pinfunction "2_2") (pintype "passive"))
      (node (ref "R80") (pin "2") (pinfunction "2_2") (pintype "passive"))
      (node (ref "R81") (pin "1") (pinfunction "1_1") (pintype "passive"))
    )
    (net (code "39") (name "Net-(R60-Pad1)") (class "Default")
      (node (ref "R60") (pin "1") (pinfunction "1_1") (pintype "passive"))
      (node (ref "R81") (pin "2") (pinfunction "2_2") (pintype "passive"))
    )
    (net (code "40") (name "Net-(R60-Pad2)") (class "Default")
      (node (ref "R60") (pin "2") (pinfunction "2_2") (pintype "passive"))
      (node (ref "R61") (pin "1") (pinfunction "1_1") (pintype "passive"))
    )
    (net (code "41") (name "Net-(R62-Pad2)") (class "Default")
      (node (ref "R62") (pin "2") (pinfunction "2_2") (pintype "passive"))
      (node (ref "R86") (pin "1") (pinfunction "1_1") (pintype "passive"))
    )
    (net (code "42") (name "Net-(R90-Pad1)") (class "Default")
      (node (ref "R90") (pin "1") (pinfunction "1_1") (pintype "passive"))
      (node (ref "R93") (pin "2") (pinfunction "2_2") (pintype "passive"))
    )
    (net (code "43") (name "P3V3Ap") (class "Default")
      (node (ref "R75") (pin "2") (pinfunction "2_2") (pintype "passive"))
    )
    (net (code "44") (name "P5V0Ap") (class "Default")
      (node (ref "C21") (pin "2") (pinfunction "2_2") (pintype "passive"))
      (node (ref "C22") (pin "2") (pinfunction "2_2") (pintype "passive"))
      (node (ref "C29") (pin "2") (pinfunction "2_2") (pintype "passive"))
      (node (ref "C48") (pin "2") (pinfunction "2_2") (pintype "passive"))
      (node (ref "IC11") (pin "8") (pinfunction "+V_8") (pintype "power_in"))
      (node (ref "IC13") (pin "8") (pinfunction "+V_8") (pintype "power_in"))
      (node (ref "IC14") (pin "8") (pinfunction "+V_8") (pintype "power_in"))
      (node (ref "IC22") (pin "5") (pinfunction "VCC_5") (pintype "power_in"))
      (node (ref "L1") (pin "1") (pinfunction "1_1") (pintype "passive"))
    )
  )
)
